# main.net
KiCad netlist of a schematic drawn in Altium Designer
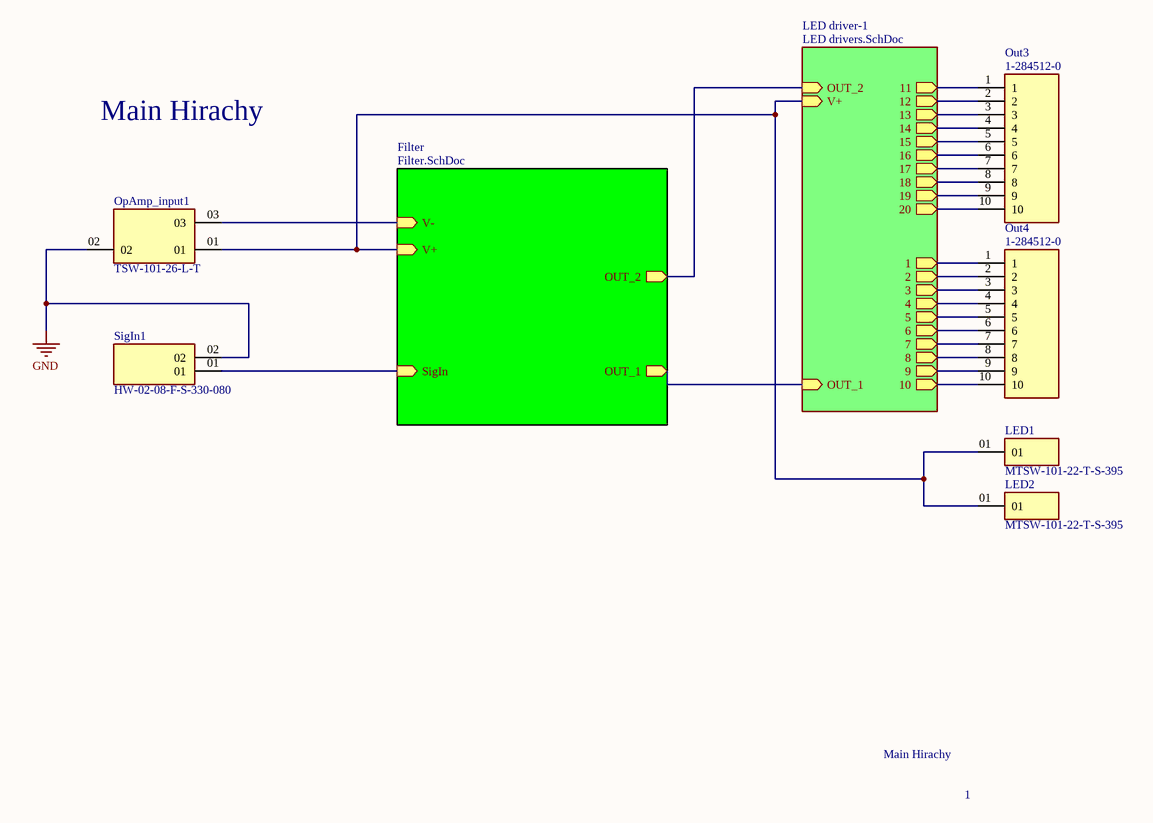
[diagram p0: main.SchDoc]

(export (version "E")
  (design (tool "Eeschema 10.0.6"))
  (components
    (comp (ref "LED1")
      (value "MTSW-101-22-T-S-395")
      (footprint "SAMTEC_MTSW-101-22-T-S-395")
      (description "Connector Header Through Hole 1 position")
      (fields (field (name "MF") "Samtec"))
      (libsource (lib "MTSW-101-22-T-S-395") (part "MTSW-101-22-T-S-395"))
    )
    (comp (ref "LED2")
      (value "MTSW-101-22-T-S-395")
      (footprint "SAMTEC_MTSW-101-22-T-S-395")
      (description "Connector Header Through Hole 1 position")
      (fields (field (name "MF") "Samtec"))
      (libsource (lib "MTSW-101-22-T-S-395") (part "MTSW-101-22-T-S-395"))
    )
    (comp (ref "OpAmp_input1")
      (value "TSW-101-26-L-T")
      (footprint "SAMTEC_TSW-101-26-L-T")
      (libsource (lib "TSW-101-26-L-T") (part "TSW-101-26-L-T"))
    )
    (comp (ref "Out3")
      (value "1-284512-0")
      (footprint "TE_1-284512-0")
      (description "10 POS TERMI-BLOK HDR 900 POLA")
      (fields (field (name "MF") "TE Connectivity"))
      (libsource (lib "1-284512-0") (part "1-284512-0"))
    )
    (comp (ref "Out4")
      (value "1-284512-0")
      (footprint "TE_1-284512-0")
      (description "10 POS TERMI-BLOK HDR 900 POLA")
      (fields (field (name "MF") "TE Connectivity"))
      (libsource (lib "1-284512-0") (part "1-284512-0"))
    )
    (comp (ref "SigIn1")
      (value "HW-02-08-F-S-330-080")
      (footprint "SAMTEC_HW-02-08-F-S-330-080")
      (libsource (lib "HW-02-08-F-S-330-080") (part "HW-02-08-F-S-330-080"))
    )
  )
  (nets
    (net (code "1") (name "/1") (class "Default")
      (node (ref "Out4") (pin "1") (pinfunction "1_1") (pintype "passive"))
    )
    (net (code "2") (name "/2") (class "Default")
      (node (ref "Out4") (pin "2") (pinfunction "2_2") (pintype "passive"))
    )
    (net (code "3") (name "/3") (class "Default")
      (node (ref "Out4") (pin "3") (pinfunction "3_3") (pintype "passive"))
    )
    (net (code "4") (name "/4") (class "Default")
      (node (ref "Out4") (pin "4") (pinfunction "4_4") (pintype "passive"))
    )
    (net (code "5") (name "/5") (class "Default")
      (node (ref "Out4") (pin "5") (pinfunction "5_5") (pintype "passive"))
    )
    (net (code "6") (name "/6") (class "Default")
      (node (ref "Out4") (pin "6") (pinfunction "6_6") (pintype "passive"))
    )
    (net (code "7") (name "/7") (class "Default")
      (node (ref "Out4") (pin "7") (pinfunction "7_7") (pintype "passive"))
    )
    (net (code "8") (name "/8") (class "Default")
      (node (ref "Out4") (pin "8") (pinfunction "8_8") (pintype "passive"))
    )
    (net (code "9") (name "/9") (class "Default")
      (node (ref "Out4") (pin "9") (pinfunction "9_9") (pintype "passive"))
    )
    (net (code "10") (name "/10") (class "Default")
      (node (ref "Out4") (pin "10") (pinfunction "10_10") (pintype "passive"))
    )
    (net (code "11") (name "/11") (class "Default")
      (node (ref "Out3") (pin "1") (pinfunction "1_1") (pintype "passive"))
    )
    (net (code "12") (name "/12") (class "Default")
      (node (ref "Out3") (pin "2") (pinfunction "2_2") (pintype "passive"))
    )
    (net (code "13") (name "/13") (class "Default")
      (node (ref "Out3") (pin "3") (pinfunction "3_3") (pintype "passive"))
    )
    (net (code "14") (name "/14") (class "Default")
      (node (ref "Out3") (pin "4") (pinfunction "4_4") (pintype "passive"))
    )
    (net (code "15") (name "/15") (class "Default")
      (node (ref "Out3") (pin "5") (pinfunction "5_5") (pintype "passive"))
    )
    (net (code "16") (name "/16") (class "Default")
      (node (ref "Out3") (pin "6") (pinfunction "6_6") (pintype "passive"))
    )
    (net (code "17") (name "/17") (class "Default")
      (node (ref "Out3") (pin "7") (pinfunction "7_7") (pintype "passive"))
    )
    (net (code "18") (name "/18") (class "Default")
      (node (ref "Out3") (pin "8") (pinfunction "8_8") (pintype "passive"))
    )
    (net (code "19") (name "/19") (class "Default")
      (node (ref "Out3") (pin "9") (pinfunction "9_9") (pintype "passive"))
    )
    (net (code "20") (name "/20") (class "Default")
      (node (ref "Out3") (pin "10") (pinfunction "10_10") (pintype "passive"))
    )
    (net (code "23") (name "/SigIn") (class "Default")
      (node (ref "SigIn1") (pin "01") (pinfunction "01_01") (pintype "passive"))
    )
    (net (code "24") (name "/V+") (class "Default")
      (node (ref "LED1") (pin "01") (pinfunction "01_01") (pintype "passive"))
      (node (ref "LED2") (pin "01") (pinfunction "01_01") (pintype "passive"))
      (node (ref "OpAmp_input1") (pin "01") (pinfunction "01_01") (pintype "passive"))
    )
    (net (code "25") (name "/V-") (class "Default")
      (node (ref "OpAmp_input1") (pin "03") (pinfunction "03_03") (pintype "passive"))
    )
    (net (code "26") (name "GND") (class "Default")
      (node (ref "OpAmp_input1") (pin "02") (pinfunction "02_02") (pintype "passive"))
      (node (ref "SigIn1") (pin "02") (pinfunction "02_02") (pintype "passive"))
    )
  )
)
